# Motor_Driver_Arduino_Uno_Shield.net
KiCad netlist of a schematic drawn in EAGLE
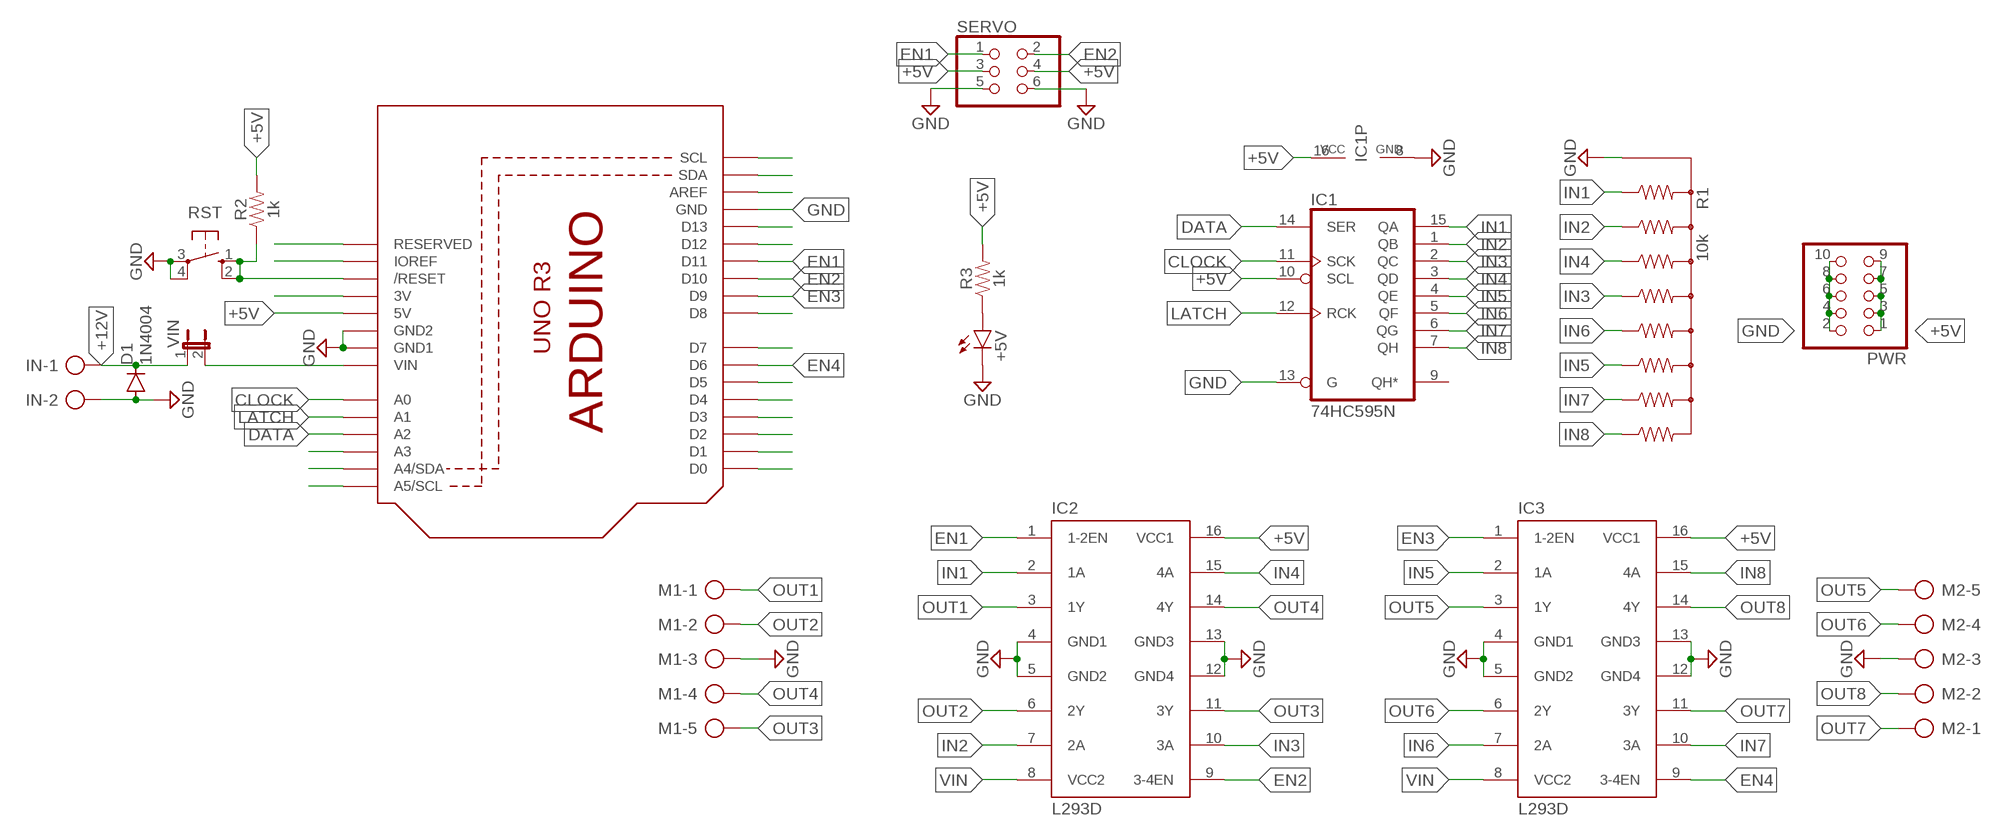
[diagram p0: schematic, sheet 1]

(export (version "E")
  (design (tool "Eeschema 10.0.6"))
  (components
    (comp (ref "+5V")
      (value "LEDCHIP-LED0805")
      (footprint "eagle-import:CHIP-LED0805")
      (libsource (lib "eagle-import") (part "LEDCHIP-LED0805"))
    )
    (comp (ref "D1")
      (value "1N4004")
      (footprint "eagle-import:DO41-10")
      (libsource (lib "eagle-import") (part "1N4004"))
    )
    (comp (ref "IC1")
      (value "74HC595N")
      (footprint "eagle-import:DIL16")
      (libsource (lib "eagle-import") (part "74595NHC"))
    )
    (comp (ref "IC2")
      (value "L293D")
      (footprint "eagle-import:DIL16")
      (libsource (lib "eagle-import") (part "L293D"))
    )
    (comp (ref "IC3")
      (value "L293D")
      (footprint "eagle-import:DIL16")
      (libsource (lib "eagle-import") (part "L293D"))
    )
    (comp (ref "IN")
      (value "AK500/2-H")
      (footprint "eagle-import:AK500_2-H")
      (libsource (lib "eagle-import") (part "AK500/2-H"))
    )
    (comp (ref "M1")
      (value "AK500/5-H")
      (footprint "eagle-import:AK500_5-H")
      (libsource (lib "eagle-import") (part "AK500/5-H"))
    )
    (comp (ref "M2")
      (value "AK500/5-H")
      (footprint "eagle-import:AK500_5-H")
      (libsource (lib "eagle-import") (part "AK500/5-H"))
    )
    (comp (ref "PWR")
      (value "PINHD-2X5")
      (footprint "eagle-import:2X05")
      (libsource (lib "eagle-import") (part "PINHD-2X5"))
    )
    (comp (ref "R1")
      (value "10k")
      (footprint "eagle-import:4609X-101-103LF")
      (fields
        (field (name "MANUFACTURER") "Bourns Inc.")
        (field (name "MPN") "4609X-101-103LF")
        (field (name "CREATED_BY") "PCBLayout.com")
      )
      (libsource (lib "eagle-import") (part "4609X-101-103LF"))
    )
    (comp (ref "R2")
      (value "1k")
      (footprint "eagle-import:1206")
      (libsource (lib "eagle-import") (part "RESISTOR1206"))
    )
    (comp (ref "R3")
      (value "1k")
      (footprint "eagle-import:1206")
      (libsource (lib "eagle-import") (part "RESISTOR1206"))
    )
    (comp (ref "RST")
      (value "10-XX")
      (footprint "eagle-import:B3F-10XX")
      (fields (field (name "MPN") "B3F-1000"))
      (libsource (lib "eagle-import") (part "10-XX"))
    )
    (comp (ref "SERVO")
      (value "PINHD-2X3")
      (footprint "eagle-import:2X03")
      (libsource (lib "eagle-import") (part "PINHD-2X3"))
    )
    (comp (ref "U1")
      (value "ARDUINOR3-BPLACE")
      (footprint "eagle-import:ARDUINOR3-BPLACE")
      (libsource (lib "eagle-import") (part "ARDUINOR3-BPLACE"))
    )
    (comp (ref "VIN")
      (value "JP1E")
      (footprint "eagle-import:JP1")
      (libsource (lib "eagle-import") (part "JP1E"))
    )
  )
  (nets
    (net (code "1") (name "+5V") (class "Default")
      (node (ref "IC1") (pin "10") (pinfunction "SCL_10") (pintype "input"))
      (node (ref "IC1") (pin "16") (pinfunction "VCC_16") (pintype "power_in"))
      (node (ref "IC2") (pin "16") (pinfunction "VCC1_16") (pintype "power_in"))
      (node (ref "IC3") (pin "16") (pinfunction "VCC1_16") (pintype "power_in"))
      (node (ref "PWR") (pin "1") (pinfunction "1_1") (pintype "passive"))
      (node (ref "PWR") (pin "3") (pinfunction "3_3") (pintype "passive"))
      (node (ref "PWR") (pin "5") (pinfunction "5_5") (pintype "passive"))
      (node (ref "PWR") (pin "7") (pinfunction "7_7") (pintype "passive"))
      (node (ref "PWR") (pin "9") (pinfunction "9_9") (pintype "passive"))
      (node (ref "R2") (pin "2") (pinfunction "2_2") (pintype "passive"))
      (node (ref "R3") (pin "2") (pinfunction "2_2") (pintype "passive"))
      (node (ref "SERVO") (pin "3") (pinfunction "3_3") (pintype "passive"))
      (node (ref "SERVO") (pin "4") (pinfunction "4_4") (pintype "passive"))
      (node (ref "U1") (pin "5V") (pinfunction "5V_5V") (pintype "power_in"))
    )
    (net (code "2") (name "+12V") (class "Default")
      (node (ref "D1") (pin "C") (pinfunction "C_C") (pintype "passive"))
      (node (ref "IN") (pin "1") (pinfunction "KL_1") (pintype "passive"))
      (node (ref "VIN") (pin "1") (pinfunction "1_1") (pintype "passive"))
    )
    (net (code "3") (name "CLOCK") (class "Default")
      (node (ref "IC1") (pin "11") (pinfunction "SCK_11") (pintype "input"))
      (node (ref "U1") (pin "A0") (pinfunction "A0_A0") (pintype "bidirectional"))
    )
    (net (code "4") (name "DATA") (class "Default")
      (node (ref "IC1") (pin "14") (pinfunction "SER_14") (pintype "input"))
      (node (ref "U1") (pin "A2") (pinfunction "A2_A2") (pintype "bidirectional"))
    )
    (net (code "5") (name "EN1") (class "Default")
      (node (ref "IC2") (pin "1") (pinfunction "1-2EN_1") (pintype "input"))
      (node (ref "SERVO") (pin "1") (pinfunction "1_1") (pintype "passive"))
      (node (ref "U1") (pin "D11") (pinfunction "D11_D11") (pintype "bidirectional"))
    )
    (net (code "6") (name "EN2") (class "Default")
      (node (ref "IC2") (pin "9") (pinfunction "3-4EN_9") (pintype "input"))
      (node (ref "SERVO") (pin "2") (pinfunction "2_2") (pintype "passive"))
      (node (ref "U1") (pin "D10") (pinfunction "D10_D10") (pintype "bidirectional"))
    )
    (net (code "7") (name "EN3") (class "Default")
      (node (ref "IC3") (pin "1") (pinfunction "1-2EN_1") (pintype "input"))
      (node (ref "U1") (pin "D9") (pinfunction "D9_D9") (pintype "bidirectional"))
    )
    (net (code "8") (name "EN4") (class "Default")
      (node (ref "IC3") (pin "9") (pinfunction "3-4EN_9") (pintype "input"))
      (node (ref "U1") (pin "D6") (pinfunction "D6_D6") (pintype "bidirectional"))
    )
    (net (code "9") (name "GND") (class "Default")
      (node (ref "+5V") (pin "C") (pinfunction "C_C") (pintype "passive"))
      (node (ref "D1") (pin "A") (pinfunction "A_A") (pintype "passive"))
      (node (ref "IC1") (pin "13") (pinfunction "G_13") (pintype "input"))
      (node (ref "IC1") (pin "8") (pinfunction "GND_8") (pintype "power_in"))
      (node (ref "IC2") (pin "12") (pinfunction "GND4_12") (pintype "power_in"))
      (node (ref "IC2") (pin "13") (pinfunction "GND3_13") (pintype "power_in"))
      (node (ref "IC2") (pin "4") (pinfunction "GND1_4") (pintype "power_in"))
      (node (ref "IC2") (pin "5") (pinfunction "GND2_5") (pintype "power_in"))
      (node (ref "IC3") (pin "12") (pinfunction "GND4_12") (pintype "power_in"))
      (node (ref "IC3") (pin "13") (pinfunction "GND3_13") (pintype "power_in"))
      (node (ref "IC3") (pin "4") (pinfunction "GND1_4") (pintype "power_in"))
      (node (ref "IC3") (pin "5") (pinfunction "GND2_5") (pintype "power_in"))
      (node (ref "IN") (pin "2") (pinfunction "KL_2") (pintype "passive"))
      (node (ref "M1") (pin "3") (pinfunction "KL_3") (pintype "passive"))
      (node (ref "M2") (pin "3") (pinfunction "KL_3") (pintype "passive"))
      (node (ref "PWR") (pin "10") (pinfunction "10_10") (pintype "passive"))
      (node (ref "PWR") (pin "2") (pinfunction "2_2") (pintype "passive"))
      (node (ref "PWR") (pin "4") (pinfunction "4_4") (pintype "passive"))
      (node (ref "PWR") (pin "6") (pinfunction "6_6") (pintype "passive"))
      (node (ref "PWR") (pin "8") (pinfunction "8_8") (pintype "passive"))
      (node (ref "R1") (pin "1") (pinfunction "1_1") (pintype "passive"))
      (node (ref "RST") (pin "3") (pinfunction "P_3") (pintype "passive"))
      (node (ref "RST") (pin "4") (pinfunction "P1_4") (pintype "passive"))
      (node (ref "SERVO") (pin "5") (pinfunction "5_5") (pintype "passive"))
      (node (ref "SERVO") (pin "6") (pinfunction "6_6") (pintype "passive"))
      (node (ref "U1") (pin "GND") (pinfunction "GND_GND") (pintype "power_in"))
      (node (ref "U1") (pin "GND1") (pinfunction "GND1_GND1") (pintype "power_in"))
      (node (ref "U1") (pin "GND2") (pinfunction "GND2_GND2") (pintype "power_in"))
    )
    (net (code "10") (name "IN1") (class "Default")
      (node (ref "IC1") (pin "15") (pinfunction "QA_15") (pintype "tri_state"))
      (node (ref "IC2") (pin "2") (pinfunction "1A_2") (pintype "input"))
      (node (ref "R1") (pin "2") (pinfunction "2_2") (pintype "passive"))
    )
    (net (code "11") (name "IN2") (class "Default")
      (node (ref "IC1") (pin "1") (pinfunction "QB_1") (pintype "tri_state"))
      (node (ref "IC2") (pin "7") (pinfunction "2A_7") (pintype "input"))
      (node (ref "R1") (pin "3") (pinfunction "3_3") (pintype "passive"))
    )
    (net (code "12") (name "IN3") (class "Default")
      (node (ref "IC1") (pin "2") (pinfunction "QC_2") (pintype "tri_state"))
      (node (ref "IC2") (pin "10") (pinfunction "3A_10") (pintype "input"))
      (node (ref "R1") (pin "5") (pinfunction "5_5") (pintype "passive"))
    )
    (net (code "13") (name "IN4") (class "Default")
      (node (ref "IC1") (pin "3") (pinfunction "QD_3") (pintype "tri_state"))
      (node (ref "IC2") (pin "15") (pinfunction "4A_15") (pintype "input"))
      (node (ref "R1") (pin "4") (pinfunction "4_4") (pintype "passive"))
    )
    (net (code "14") (name "IN5") (class "Default")
      (node (ref "IC1") (pin "4") (pinfunction "QE_4") (pintype "tri_state"))
      (node (ref "IC3") (pin "2") (pinfunction "1A_2") (pintype "input"))
      (node (ref "R1") (pin "7") (pinfunction "7_7") (pintype "passive"))
    )
    (net (code "15") (name "IN6") (class "Default")
      (node (ref "IC1") (pin "5") (pinfunction "QF_5") (pintype "tri_state"))
      (node (ref "IC3") (pin "7") (pinfunction "2A_7") (pintype "input"))
      (node (ref "R1") (pin "6") (pinfunction "6_6") (pintype "passive"))
    )
    (net (code "16") (name "IN7") (class "Default")
      (node (ref "IC1") (pin "6") (pinfunction "QG_6") (pintype "tri_state"))
      (node (ref "IC3") (pin "10") (pinfunction "3A_10") (pintype "input"))
      (node (ref "R1") (pin "8") (pinfunction "8_8") (pintype "passive"))
    )
    (net (code "17") (name "IN8") (class "Default")
      (node (ref "IC1") (pin "7") (pinfunction "QH_7") (pintype "tri_state"))
      (node (ref "IC3") (pin "15") (pinfunction "4A_15") (pintype "input"))
      (node (ref "R1") (pin "9") (pinfunction "9_9") (pintype "passive"))
    )
    (net (code "18") (name "LATCH") (class "Default")
      (node (ref "IC1") (pin "12") (pinfunction "RCK_12") (pintype "input"))
      (node (ref "U1") (pin "A1") (pinfunction "A1_A1") (pintype "bidirectional"))
    )
    (net (code "19") (name "Net-(+5V-PadA)") (class "Default")
      (node (ref "+5V") (pin "A") (pinfunction "A_A") (pintype "passive"))
      (node (ref "R3") (pin "1") (pinfunction "1_1") (pintype "passive"))
    )
    (net (code "20") (name "Net-(RST-S)") (class "Default")
      (node (ref "R2") (pin "1") (pinfunction "1_1") (pintype "passive"))
      (node (ref "RST") (pin "1") (pinfunction "S_1") (pintype "passive"))
      (node (ref "RST") (pin "2") (pinfunction "S1_2") (pintype "passive"))
      (node (ref "U1") (pin "RESET") (pinfunction "/RESET_RESET") (pintype "bidirectional"))
    )
    (net (code "21") (name "OUT1") (class "Default")
      (node (ref "IC2") (pin "3") (pinfunction "1Y_3") (pintype "output"))
      (node (ref "M1") (pin "1") (pinfunction "KL_1") (pintype "passive"))
    )
    (net (code "22") (name "OUT2") (class "Default")
      (node (ref "IC2") (pin "6") (pinfunction "2Y_6") (pintype "output"))
      (node (ref "M1") (pin "2") (pinfunction "KL_2") (pintype "passive"))
    )
    (net (code "23") (name "OUT3") (class "Default")
      (node (ref "IC2") (pin "11") (pinfunction "3Y_11") (pintype "output"))
      (node (ref "M1") (pin "5") (pinfunction "KL_5") (pintype "passive"))
    )
    (net (code "24") (name "OUT4") (class "Default")
      (node (ref "IC2") (pin "14") (pinfunction "4Y_14") (pintype "output"))
      (node (ref "M1") (pin "4") (pinfunction "KL_4") (pintype "passive"))
    )
    (net (code "25") (name "OUT5") (class "Default")
      (node (ref "IC3") (pin "3") (pinfunction "1Y_3") (pintype "output"))
      (node (ref "M2") (pin "5") (pinfunction "KL_5") (pintype "passive"))
    )
    (net (code "26") (name "OUT6") (class "Default")
      (node (ref "IC3") (pin "6") (pinfunction "2Y_6") (pintype "output"))
      (node (ref "M2") (pin "4") (pinfunction "KL_4") (pintype "passive"))
    )
    (net (code "27") (name "OUT7") (class "Default")
      (node (ref "IC3") (pin "11") (pinfunction "3Y_11") (pintype "output"))
      (node (ref "M2") (pin "1") (pinfunction "KL_1") (pintype "passive"))
    )
    (net (code "28") (name "OUT8") (class "Default")
      (node (ref "IC3") (pin "14") (pinfunction "4Y_14") (pintype "output"))
      (node (ref "M2") (pin "2") (pinfunction "KL_2") (pintype "passive"))
    )
    (net (code "29") (name "VIN") (class "Default")
      (node (ref "IC2") (pin "8") (pinfunction "VCC2_8") (pintype "power_in"))
      (node (ref "IC3") (pin "8") (pinfunction "VCC2_8") (pintype "power_in"))
      (node (ref "U1") (pin "VIN") (pinfunction "VIN_VIN") (pintype "power_in"))
      (node (ref "VIN") (pin "2") (pinfunction "2_2") (pintype "passive"))
    )
    (net (code "30") (name "unconnected-(IC1A-QH*-Pad9)") (class "Default")
      (node (ref "IC1") (pin "9") (pinfunction "QH*_9") (pintype "tri_state"))
    )
    (net (code "31") (name "unconnected-(U1-A4{slash}SDA-PadA4)") (class "Default")
      (node (ref "U1") (pin "A4") (pinfunction "A4/SDA_A4") (pintype "bidirectional"))
    )
    (net (code "32") (name "unconnected-(U1-A5{slash}SCL-PadA5)") (class "Default")
      (node (ref "U1") (pin "A5") (pinfunction "A5/SCL_A5") (pintype "bidirectional"))
    )
    (net (code "33") (name "unconnected-(U1-Pad3V)") (class "Default")
      (node (ref "U1") (pin "3V") (pinfunction "3V_3V") (pintype "power_in"))
    )
    (net (code "34") (name "unconnected-(U1-PadA3)") (class "Default")
      (node (ref "U1") (pin "A3") (pinfunction "A3_A3") (pintype "bidirectional"))
    )
    (net (code "35") (name "unconnected-(U1-PadAREF)") (class "Default")
      (node (ref "U1") (pin "AREF") (pinfunction "AREF_AREF") (pintype "bidirectional"))
    )
    (net (code "36") (name "unconnected-(U1-PadD0)") (class "Default")
      (node (ref "U1") (pin "D0") (pinfunction "D0_D0") (pintype "bidirectional"))
    )
    (net (code "37") (name "unconnected-(U1-PadD1)") (class "Default")
      (node (ref "U1") (pin "D1") (pinfunction "D1_D1") (pintype "bidirectional"))
    )
    (net (code "38") (name "unconnected-(U1-PadD2)") (class "Default")
      (node (ref "U1") (pin "D2") (pinfunction "D2_D2") (pintype "bidirectional"))
    )
    (net (code "39") (name "unconnected-(U1-PadD3)") (class "Default")
      (node (ref "U1") (pin "D3") (pinfunction "D3_D3") (pintype "bidirectional"))
    )
    (net (code "40") (name "unconnected-(U1-PadD4)") (class "Default")
      (node (ref "U1") (pin "D4") (pinfunction "D4_D4") (pintype "bidirectional"))
    )
    (net (code "41") (name "unconnected-(U1-PadD5)") (class "Default")
      (node (ref "U1") (pin "D5") (pinfunction "D5_D5") (pintype "bidirectional"))
    )
    (net (code "42") (name "unconnected-(U1-PadD7)") (class "Default")
      (node (ref "U1") (pin "D7") (pinfunction "D7_D7") (pintype "bidirectional"))
    )
    (net (code "43") (name "unconnected-(U1-PadD8)") (class "Default")
      (node (ref "U1") (pin "D8") (pinfunction "D8_D8") (pintype "bidirectional"))
    )
    (net (code "44") (name "unconnected-(U1-PadD12)") (class "Default")
      (node (ref "U1") (pin "D12") (pinfunction "D12_D12") (pintype "bidirectional"))
    )
    (net (code "45") (name "unconnected-(U1-PadD13)") (class "Default")
      (node (ref "U1") (pin "D13") (pinfunction "D13_D13") (pintype "bidirectional"))
    )
    (net (code "46") (name "unconnected-(U1-PadIOREF)") (class "Default")
      (node (ref "U1") (pin "IOREF") (pinfunction "IOREF_IOREF") (pintype "output"))
    )
    (net (code "47") (name "unconnected-(U1-PadRESERVED)") (class "Default")
      (node (ref "U1") (pin "RESERVED") (pinfunction "RESERVED_RESERVED") (pintype "no_connect"))
    )
    (net (code "48") (name "unconnected-(U1-PadSCL)") (class "Default")
      (node (ref "U1") (pin "SCL") (pinfunction "SCL_SCL") (pintype "bidirectional"))
    )
    (net (code "49") (name "unconnected-(U1-PadSDA)") (class "Default")
      (node (ref "U1") (pin "SDA") (pinfunction "SDA_SDA") (pintype "bidirectional"))
    )
  )
)
